# LoRa_RFM95_Shield.net
KiCad netlist of a schematic drawn in EAGLE
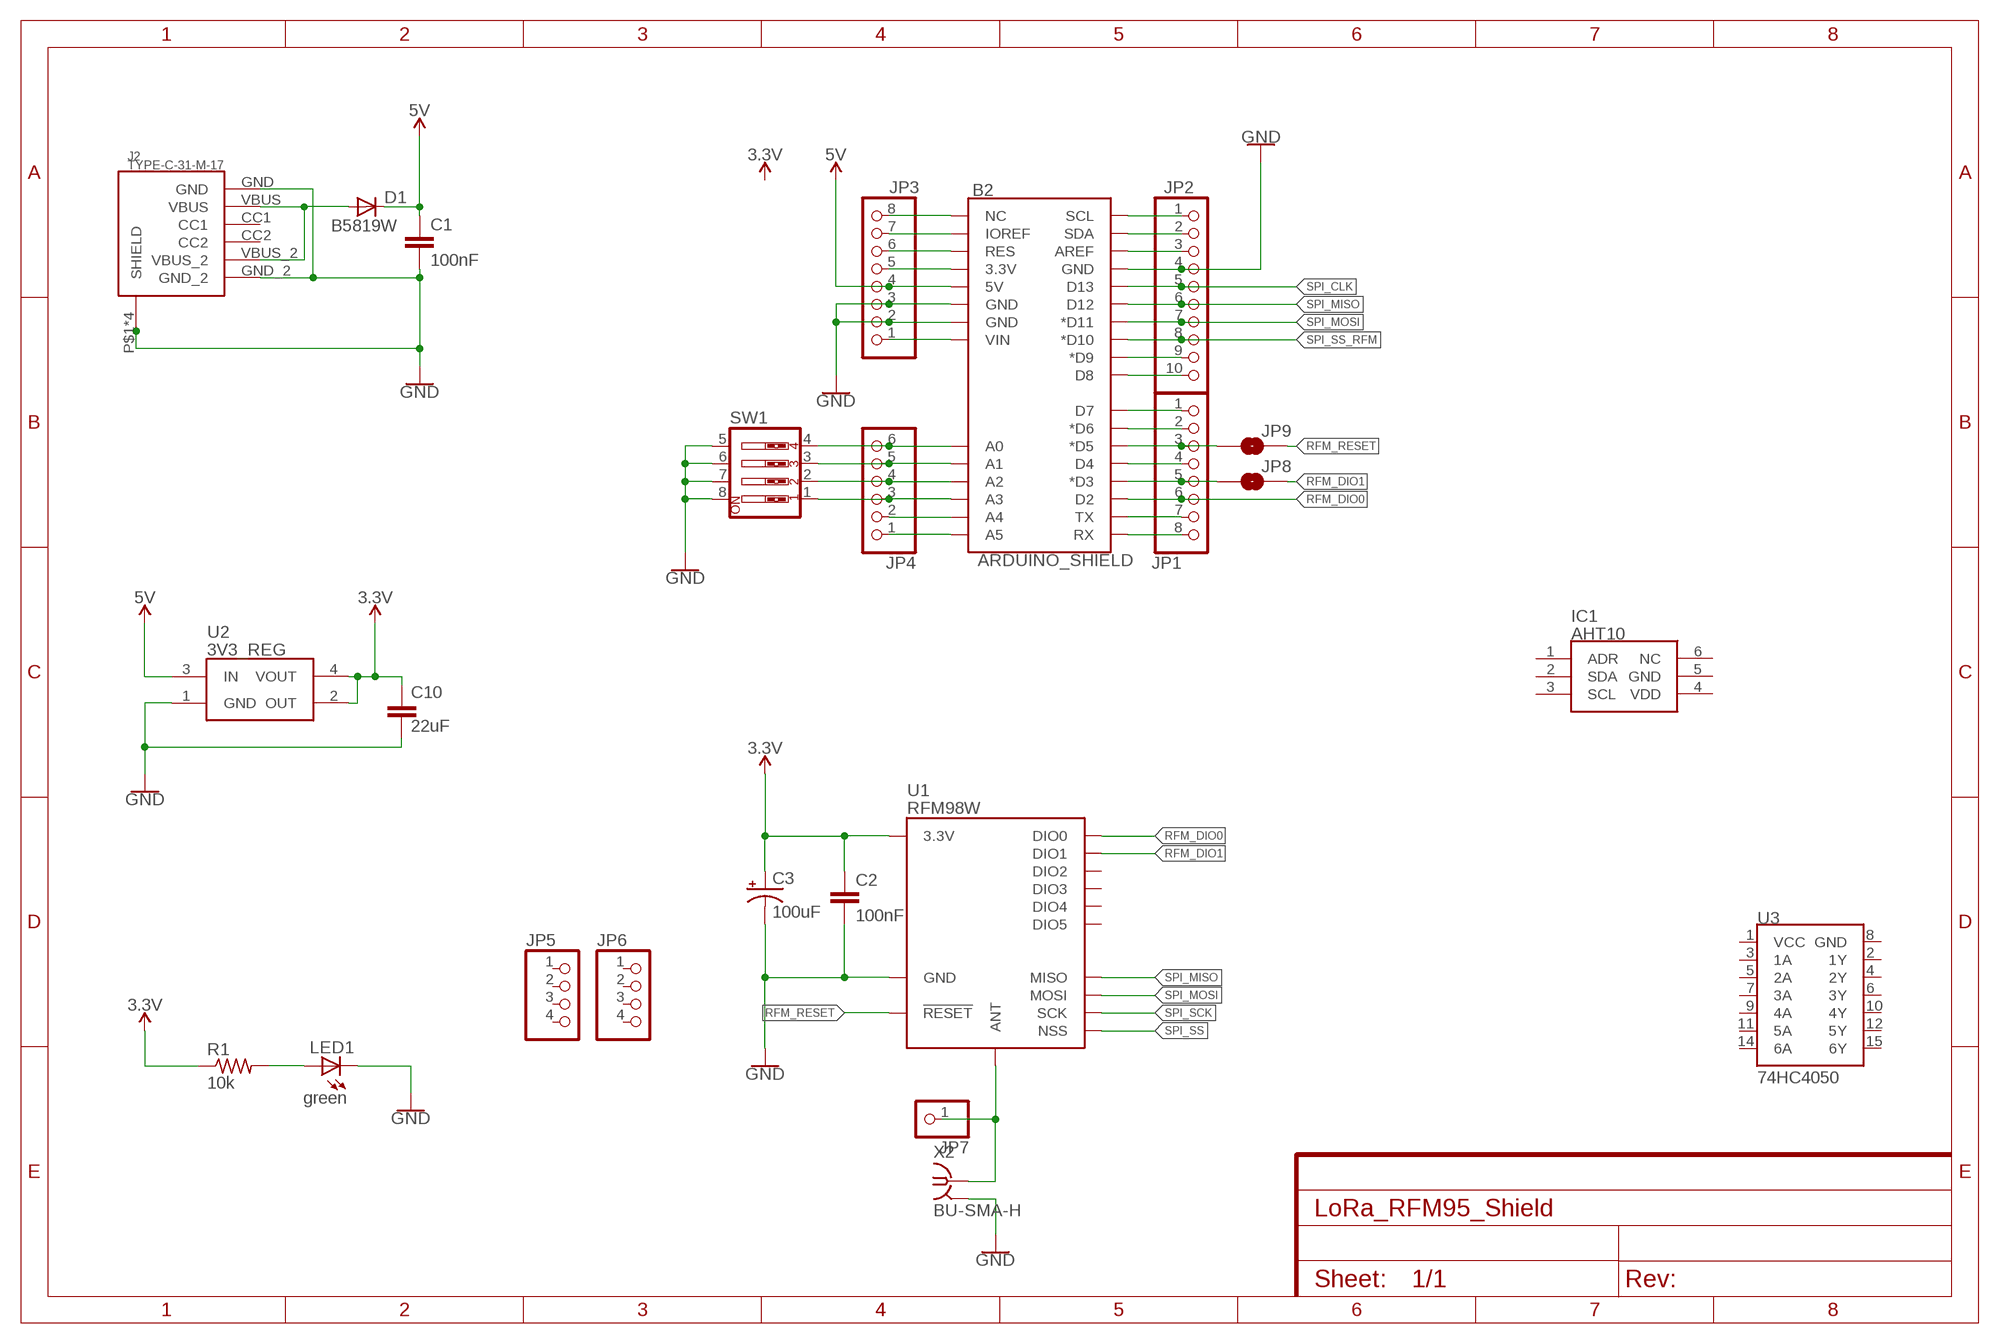
[diagram p0: schematic, sheet 1]

(export (version "E")
  (design (tool "Eeschema 10.0.6"))
  (components
    (comp (ref "B2")
      (value "ARDUINO_SHIELD")
      (footprint "eagle-import:UNO_R3_SHIELD_NOLABELS_LOCK")
      (libsource (lib "eagle-import") (part "ARDUINO_UNO_R3_SHIELDUNO_R3_SHIELD_NOLABELS_LOCK"))
    )
    (comp (ref "C1")
      (value "100nF")
      (footprint "eagle-import:C0603")
      (libsource (lib "eagle-import") (part "C-EUC0603"))
    )
    (comp (ref "C2")
      (value "100nF")
      (footprint "eagle-import:C0603")
      (libsource (lib "eagle-import") (part "C-EUC0603"))
    )
    (comp (ref "C3")
      (value "100uF")
      (footprint "eagle-import:SMC_B")
      (libsource (lib "eagle-import") (part "CPOL-USSMCB"))
    )
    (comp (ref "C10")
      (value "22uF")
      (footprint "eagle-import:C0805")
      (libsource (lib "eagle-import") (part "C-EUC0805"))
    )
    (comp (ref "D1")
      (value "B5819W")
      (footprint "eagle-import:SOD-123")
      (libsource (lib "eagle-import") (part "DIODE-SOD-123"))
    )
    (comp (ref "IC1")
      (value "AHT10")
      (footprint "eagle-import:AHT10")
      (libsource (lib "eagle-import") (part "AHT10"))
    )
    (comp (ref "J2")
      (value "TYPE-C-31-M-17")
      (footprint "eagle-import:TYPE-C-31-M-17")
      (libsource (lib "eagle-import") (part "TYPE-C-31-M-17"))
    )
    (comp (ref "JP1")
      (value "PINHD-1X8/OCT")
      (footprint "eagle-import:1X08_OCT")
      (libsource (lib "eagle-import") (part "PINHD-1X8/OCT"))
    )
    (comp (ref "JP2")
      (value "PINHD-1X10/OCT")
      (footprint "eagle-import:1X10_OCT")
      (libsource (lib "eagle-import") (part "PINHD-1X10/OCT"))
    )
    (comp (ref "JP3")
      (value "PINHD-1X8/OCT")
      (footprint "eagle-import:1X08_OCT")
      (libsource (lib "eagle-import") (part "PINHD-1X8/OCT"))
    )
    (comp (ref "JP4")
      (value "PINHD-1X6/OCT")
      (footprint "eagle-import:1X06_OCT")
      (libsource (lib "eagle-import") (part "PINHD-1X6/OCT"))
    )
    (comp (ref "JP5")
      (value "PINHD-1X4/OCT")
      (footprint "eagle-import:1X04_OCT")
      (libsource (lib "eagle-import") (part "PINHD-1X4/OCT"))
    )
    (comp (ref "JP6")
      (value "PINHD-1X4/OCT")
      (footprint "eagle-import:1X04_OCT")
      (libsource (lib "eagle-import") (part "PINHD-1X4/OCT"))
    )
    (comp (ref "JP7")
      (value "PINHD-1X1/OCT")
      (footprint "eagle-import:1X01_OCT")
      (libsource (lib "eagle-import") (part "PINHD-1X1/OCT"))
    )
    (comp (ref "JP8")
      (value "JUMPER-SMT_2_NO_SILK")
      (footprint "eagle-import:SMT-JUMPER_2_NO_SILK")
      (libsource (lib "eagle-import") (part "JUMPER-SMT_2_NO_SILK"))
    )
    (comp (ref "JP9")
      (value "JUMPER-SMT_2_NO_SILK")
      (footprint "eagle-import:SMT-JUMPER_2_NO_SILK")
      (libsource (lib "eagle-import") (part "JUMPER-SMT_2_NO_SILK"))
    )
    (comp (ref "LED1")
      (value "green")
      (footprint "eagle-import:CHIP-LED0603")
      (libsource (lib "eagle-import") (part "LEDCHIP-LED0603"))
    )
    (comp (ref "R1")
      (value "10k")
      (footprint "eagle-import:R0603")
      (libsource (lib "eagle-import") (part "R-US_R0603"))
    )
    (comp (ref "SW1")
      (value "SW_DIP-4")
      (footprint "eagle-import:EDG-04")
      (libsource (lib "eagle-import") (part "SW_DIP-4"))
    )
    (comp (ref "U1")
      (value "RFM98W")
      (footprint "eagle-import:RFM95_96_97_98W")
      (libsource (lib "eagle-import") (part "RFM95W"))
    )
    (comp (ref "U2")
      (value "3V3_REG")
      (footprint "eagle-import:SOT230P700X170-4N")
      (fields
        (field (name "MANUFACTURER_PART_NUMBER") "AZ1117H-5.0TRE1")
        (field (name "MOUSER_PART_NUMBER") "621-AZ1117H-5.0TRE1")
      )
      (libsource (lib "eagle-import") (part "AZ1117H-5.0TRE1"))
    )
    (comp (ref "U3")
      (value "74HC4050")
      (footprint "eagle-import:SO16")
      (libsource (lib "eagle-import") (part "HEX_CONVERTER"))
    )
    (comp (ref "X2")
      (value "BU-SMA-H")
      (footprint "eagle-import:BU-SMA-H")
      (libsource (lib "eagle-import") (part "BU-SMA-H"))
    )
  )
  (nets
    (net (code "1") (name "3.3V") (class "Default")
      (node (ref "C10") (pin "2") (pinfunction "2_2") (pintype "passive"))
      (node (ref "C2") (pin "1") (pinfunction "1_1") (pintype "passive"))
      (node (ref "C3") (pin "+") (pinfunction "+_+") (pintype "passive"))
      (node (ref "R1") (pin "1") (pinfunction "1_1") (pintype "passive"))
      (node (ref "U1") (pin "3.3V") (pinfunction "3.3V_3.3V") (pintype "bidirectional"))
      (node (ref "U2") (pin "2") (pinfunction "OUT_2") (pintype "bidirectional"))
      (node (ref "U2") (pin "4") (pinfunction "VOUT_4") (pintype "bidirectional"))
    )
    (net (code "2") (name "5V") (class "Default")
      (node (ref "B2") (pin "5V") (pinfunction "5V_5V") (pintype "bidirectional"))
      (node (ref "C1") (pin "1") (pinfunction "1_1") (pintype "passive"))
      (node (ref "D1") (pin "C") (pinfunction "C_C") (pintype "passive"))
      (node (ref "JP3") (pin "4") (pinfunction "4_4") (pintype "passive"))
      (node (ref "U2") (pin "3") (pinfunction "IN_3") (pintype "bidirectional"))
    )
    (net (code "3") (name "GND") (class "Default")
      (node (ref "B2") (pin "GND@0") (pinfunction "GND_GND@0") (pintype "bidirectional"))
      (node (ref "B2") (pin "GND@1") (pinfunction "GND_GND@1") (pintype "bidirectional"))
      (node (ref "B2") (pin "GND@2") (pinfunction "GND_GND@2") (pintype "bidirectional"))
      (node (ref "C1") (pin "2") (pinfunction "2_2") (pintype "passive"))
      (node (ref "C10") (pin "1") (pinfunction "1_1") (pintype "passive"))
      (node (ref "C2") (pin "2") (pinfunction "2_2") (pintype "passive"))
      (node (ref "C3") (pin "-") (pinfunction "-_-") (pintype "passive"))
      (node (ref "J2") (pin "GND") (pinfunction "GND_GND") (pintype "bidirectional"))
      (node (ref "J2") (pin "GND_2") (pinfunction "GND_2_GND_2") (pintype "bidirectional"))
      (node (ref "J2") (pin "P$1") (pinfunction "SHIELD_P$1") (pintype "bidirectional"))
      (node (ref "J2") (pin "P$2") (pinfunction "SHIELD_P$2") (pintype "bidirectional"))
      (node (ref "J2") (pin "P$3") (pinfunction "SHIELD_P$3") (pintype "bidirectional"))
      (node (ref "J2") (pin "P$4") (pinfunction "SHIELD_P$4") (pintype "bidirectional"))
      (node (ref "JP2") (pin "4") (pinfunction "4_4") (pintype "passive"))
      (node (ref "JP3") (pin "2") (pinfunction "2_2") (pintype "passive"))
      (node (ref "JP3") (pin "3") (pinfunction "3_3") (pintype "passive"))
      (node (ref "LED1") (pin "C") (pinfunction "C_C") (pintype "passive"))
      (node (ref "SW1") (pin "5") (pinfunction "5_5") (pintype "passive"))
      (node (ref "SW1") (pin "6") (pinfunction "6_6") (pintype "passive"))
      (node (ref "SW1") (pin "7") (pinfunction "7_7") (pintype "passive"))
      (node (ref "SW1") (pin "8") (pinfunction "8_8") (pintype "passive"))
      (node (ref "U1") (pin "GND@1") (pinfunction "GND_GND@1") (pintype "bidirectional"))
      (node (ref "U1") (pin "GND@2") (pinfunction "GND_GND@2") (pintype "bidirectional"))
      (node (ref "U1") (pin "GND@3") (pinfunction "GND_GND@3") (pintype "bidirectional"))
      (node (ref "U2") (pin "1") (pinfunction "GND_1") (pintype "bidirectional"))
      (node (ref "X2") (pin "2") (pinfunction "2_2") (pintype "passive"))
      (node (ref "X2") (pin "3") (pinfunction "2_3") (pintype "passive"))
      (node (ref "X2") (pin "4") (pinfunction "2_4") (pintype "passive"))
      (node (ref "X2") (pin "5") (pinfunction "2_5") (pintype "passive"))
    )
    (net (code "4") (name "Net-(B2-*D3)") (class "Default")
      (node (ref "B2") (pin "D3") (pinfunction "*D3_D3") (pintype "bidirectional"))
      (node (ref "JP1") (pin "5") (pinfunction "5_5") (pintype "passive"))
      (node (ref "JP8") (pin "1") (pinfunction "1_1") (pintype "passive"))
    )
    (net (code "5") (name "Net-(B2-*D5)") (class "Default")
      (node (ref "B2") (pin "D5") (pinfunction "*D5_D5") (pintype "bidirectional"))
      (node (ref "JP1") (pin "3") (pinfunction "3_3") (pintype "passive"))
      (node (ref "JP9") (pin "1") (pinfunction "1_1") (pintype "passive"))
    )
    (net (code "6") (name "Net-(B2-*D6)") (class "Default")
      (node (ref "B2") (pin "D6") (pinfunction "*D6_D6") (pintype "bidirectional"))
      (node (ref "JP1") (pin "2") (pinfunction "2_2") (pintype "passive"))
    )
    (net (code "7") (name "Net-(B2-*D9)") (class "Default")
      (node (ref "B2") (pin "D9") (pinfunction "*D9_D9") (pintype "bidirectional"))
      (node (ref "JP2") (pin "9") (pinfunction "9_9") (pintype "passive"))
    )
    (net (code "8") (name "Net-(B2-Pad3.3V)") (class "Default")
      (node (ref "B2") (pin "3.3V") (pinfunction "3.3V_3.3V") (pintype "bidirectional"))
      (node (ref "JP3") (pin "5") (pinfunction "5_5") (pintype "passive"))
    )
    (net (code "9") (name "Net-(B2-PadA0)") (class "Default")
      (node (ref "B2") (pin "A0") (pinfunction "A0_A0") (pintype "bidirectional"))
      (node (ref "JP4") (pin "6") (pinfunction "6_6") (pintype "passive"))
      (node (ref "SW1") (pin "4") (pinfunction "4_4") (pintype "passive"))
    )
    (net (code "10") (name "Net-(B2-PadA1)") (class "Default")
      (node (ref "B2") (pin "A1") (pinfunction "A1_A1") (pintype "bidirectional"))
      (node (ref "JP4") (pin "5") (pinfunction "5_5") (pintype "passive"))
      (node (ref "SW1") (pin "3") (pinfunction "3_3") (pintype "passive"))
    )
    (net (code "11") (name "Net-(B2-PadA2)") (class "Default")
      (node (ref "B2") (pin "A2") (pinfunction "A2_A2") (pintype "bidirectional"))
      (node (ref "JP4") (pin "4") (pinfunction "4_4") (pintype "passive"))
      (node (ref "SW1") (pin "2") (pinfunction "2_2") (pintype "passive"))
    )
    (net (code "12") (name "Net-(B2-PadA3)") (class "Default")
      (node (ref "B2") (pin "A3") (pinfunction "A3_A3") (pintype "bidirectional"))
      (node (ref "JP4") (pin "3") (pinfunction "3_3") (pintype "passive"))
      (node (ref "SW1") (pin "1") (pinfunction "1_1") (pintype "passive"))
    )
    (net (code "13") (name "Net-(B2-PadA4)") (class "Default")
      (node (ref "B2") (pin "A4") (pinfunction "A4_A4") (pintype "bidirectional"))
      (node (ref "JP4") (pin "2") (pinfunction "2_2") (pintype "passive"))
    )
    (net (code "14") (name "Net-(B2-PadA5)") (class "Default")
      (node (ref "B2") (pin "A5") (pinfunction "A5_A5") (pintype "bidirectional"))
      (node (ref "JP4") (pin "1") (pinfunction "1_1") (pintype "passive"))
    )
    (net (code "15") (name "Net-(B2-PadAREF)") (class "Default")
      (node (ref "B2") (pin "AREF") (pinfunction "AREF_AREF") (pintype "bidirectional"))
      (node (ref "JP2") (pin "3") (pinfunction "3_3") (pintype "passive"))
    )
    (net (code "16") (name "Net-(B2-PadD4)") (class "Default")
      (node (ref "B2") (pin "D4") (pinfunction "D4_D4") (pintype "bidirectional"))
      (node (ref "JP1") (pin "4") (pinfunction "4_4") (pintype "passive"))
    )
    (net (code "17") (name "Net-(B2-PadD7)") (class "Default")
      (node (ref "B2") (pin "D7") (pinfunction "D7_D7") (pintype "bidirectional"))
      (node (ref "JP1") (pin "1") (pinfunction "1_1") (pintype "passive"))
    )
    (net (code "18") (name "Net-(B2-PadD8)") (class "Default")
      (node (ref "B2") (pin "D8") (pinfunction "D8_D8") (pintype "bidirectional"))
      (node (ref "JP2") (pin "10") (pinfunction "10_10") (pintype "passive"))
    )
    (net (code "19") (name "Net-(B2-PadIOREF)") (class "Default")
      (node (ref "B2") (pin "IOREF") (pinfunction "IOREF_IOREF") (pintype "bidirectional"))
      (node (ref "JP3") (pin "7") (pinfunction "7_7") (pintype "passive"))
    )
    (net (code "20") (name "Net-(B2-PadNC)") (class "Default")
      (node (ref "B2") (pin "NC") (pinfunction "NC_NC") (pintype "bidirectional"))
      (node (ref "JP3") (pin "8") (pinfunction "8_8") (pintype "passive"))
    )
    (net (code "21") (name "Net-(B2-PadRES)") (class "Default")
      (node (ref "B2") (pin "RES") (pinfunction "RES_RES") (pintype "bidirectional"))
      (node (ref "JP3") (pin "6") (pinfunction "6_6") (pintype "passive"))
    )
    (net (code "22") (name "Net-(B2-PadRX)") (class "Default")
      (node (ref "B2") (pin "RX") (pinfunction "RX_RX") (pintype "bidirectional"))
      (node (ref "JP1") (pin "8") (pinfunction "8_8") (pintype "passive"))
    )
    (net (code "23") (name "Net-(B2-PadSCL)") (class "Default")
      (node (ref "B2") (pin "SCL") (pinfunction "SCL_SCL") (pintype "bidirectional"))
      (node (ref "JP2") (pin "1") (pinfunction "1_1") (pintype "passive"))
    )
    (net (code "24") (name "Net-(B2-PadSDA)") (class "Default")
      (node (ref "B2") (pin "SDA") (pinfunction "SDA_SDA") (pintype "bidirectional"))
      (node (ref "JP2") (pin "2") (pinfunction "2_2") (pintype "passive"))
    )
    (net (code "25") (name "Net-(B2-PadTX)") (class "Default")
      (node (ref "B2") (pin "TX") (pinfunction "TX_TX") (pintype "bidirectional"))
      (node (ref "JP1") (pin "7") (pinfunction "7_7") (pintype "passive"))
    )
    (net (code "26") (name "Net-(B2-PadVIN)") (class "Default")
      (node (ref "B2") (pin "VIN") (pinfunction "VIN_VIN") (pintype "bidirectional"))
      (node (ref "JP3") (pin "1") (pinfunction "1_1") (pintype "passive"))
    )
    (net (code "27") (name "Net-(D1-PadA)") (class "Default")
      (node (ref "D1") (pin "A") (pinfunction "A_A") (pintype "passive"))
      (node (ref "J2") (pin "VBUS") (pinfunction "VBUS_VBUS") (pintype "bidirectional"))
      (node (ref "J2") (pin "VBUS_2") (pinfunction "VBUS_2_VBUS_2") (pintype "bidirectional"))
    )
    (net (code "28") (name "Net-(JP7-Pad1)") (class "Default")
      (node (ref "JP7") (pin "1") (pinfunction "1_1") (pintype "passive"))
      (node (ref "U1") (pin "ANT") (pinfunction "ANT_ANT") (pintype "bidirectional"))
      (node (ref "X2") (pin "1") (pinfunction "1_1") (pintype "passive"))
    )
    (net (code "29") (name "Net-(LED1-PadA)") (class "Default")
      (node (ref "LED1") (pin "A") (pinfunction "A_A") (pintype "passive"))
      (node (ref "R1") (pin "2") (pinfunction "2_2") (pintype "passive"))
    )
    (net (code "30") (name "RFM_DIO0") (class "Default")
      (node (ref "B2") (pin "D2") (pinfunction "D2_D2") (pintype "bidirectional"))
      (node (ref "JP1") (pin "6") (pinfunction "6_6") (pintype "passive"))
      (node (ref "U1") (pin "DIO0") (pinfunction "DIO0_DIO0") (pintype "bidirectional"))
    )
    (net (code "31") (name "RFM_DIO1") (class "Default")
      (node (ref "JP8") (pin "2") (pinfunction "2_2") (pintype "passive"))
      (node (ref "U1") (pin "DIO1") (pinfunction "DIO1_DIO1") (pintype "bidirectional"))
    )
    (net (code "32") (name "RFM_RESET") (class "Default")
      (node (ref "JP9") (pin "2") (pinfunction "2_2") (pintype "passive"))
      (node (ref "U1") (pin "!RESET") (pinfunction "~{RESET}_!RESET") (pintype "bidirectional"))
    )
    (net (code "33") (name "SPI_CLK") (class "Default")
      (node (ref "B2") (pin "D13") (pinfunction "D13_D13") (pintype "bidirectional"))
      (node (ref "JP2") (pin "5") (pinfunction "5_5") (pintype "passive"))
    )
    (net (code "34") (name "SPI_MISO") (class "Default")
      (node (ref "B2") (pin "D12") (pinfunction "D12_D12") (pintype "bidirectional"))
      (node (ref "JP2") (pin "6") (pinfunction "6_6") (pintype "passive"))
      (node (ref "U1") (pin "MISO") (pinfunction "MISO_MISO") (pintype "bidirectional"))
    )
    (net (code "35") (name "SPI_MOSI") (class "Default")
      (node (ref "B2") (pin "D11") (pinfunction "*D11_D11") (pintype "bidirectional"))
      (node (ref "JP2") (pin "7") (pinfunction "7_7") (pintype "passive"))
      (node (ref "U1") (pin "MOSI") (pinfunction "MOSI_MOSI") (pintype "bidirectional"))
    )
    (net (code "36") (name "SPI_SCK") (class "Default")
      (node (ref "U1") (pin "SCK") (pinfunction "SCK_SCK") (pintype "bidirectional"))
    )
    (net (code "37") (name "SPI_SS") (class "Default")
      (node (ref "U1") (pin "NSS") (pinfunction "NSS_NSS") (pintype "bidirectional"))
    )
    (net (code "38") (name "SPI_SS_RFM") (class "Default")
      (node (ref "B2") (pin "D10") (pinfunction "*D10_D10") (pintype "bidirectional"))
      (node (ref "JP2") (pin "8") (pinfunction "8_8") (pintype "passive"))
    )
    (net (code "39") (name "unconnected-(IC1-ADR-Pad1)") (class "Default")
      (node (ref "IC1") (pin "1") (pinfunction "ADR_1") (pintype "bidirectional"))
    )
    (net (code "40") (name "unconnected-(IC1-GND-Pad5)") (class "Default")
      (node (ref "IC1") (pin "5") (pinfunction "GND_5") (pintype "bidirectional"))
    )
    (net (code "41") (name "unconnected-(IC1-NC-Pad6)") (class "Default")
      (node (ref "IC1") (pin "6") (pinfunction "NC_6") (pintype "no_connect"))
    )
    (net (code "42") (name "unconnected-(IC1-SCL-Pad3)") (class "Default")
      (node (ref "IC1") (pin "3") (pinfunction "SCL_3") (pintype "bidirectional"))
    )
    (net (code "43") (name "unconnected-(IC1-SDA-Pad2)") (class "Default")
      (node (ref "IC1") (pin "2") (pinfunction "SDA_2") (pintype "bidirectional"))
    )
    (net (code "44") (name "unconnected-(IC1-VDD-Pad4)") (class "Default")
      (node (ref "IC1") (pin "4") (pinfunction "VDD_4") (pintype "bidirectional"))
    )
    (net (code "45") (name "unconnected-(J2-PadCC1)") (class "Default")
      (node (ref "J2") (pin "CC1") (pinfunction "CC1_CC1") (pintype "bidirectional"))
    )
    (net (code "46") (name "unconnected-(J2-PadCC2)") (class "Default")
      (node (ref "J2") (pin "CC2") (pinfunction "CC2_CC2") (pintype "bidirectional"))
    )
    (net (code "47") (name "unconnected-(JP5-Pad1)") (class "Default")
      (node (ref "JP5") (pin "1") (pinfunction "1_1") (pintype "passive"))
    )
    (net (code "48") (name "unconnected-(JP5-Pad2)") (class "Default")
      (node (ref "JP5") (pin "2") (pinfunction "2_2") (pintype "passive"))
    )
    (net (code "49") (name "unconnected-(JP5-Pad3)") (class "Default")
      (node (ref "JP5") (pin "3") (pinfunction "3_3") (pintype "passive"))
    )
    (net (code "50") (name "unconnected-(JP5-Pad4)") (class "Default")
      (node (ref "JP5") (pin "4") (pinfunction "4_4") (pintype "passive"))
    )
    (net (code "51") (name "unconnected-(JP6-Pad1)") (class "Default")
      (node (ref "JP6") (pin "1") (pinfunction "1_1") (pintype "passive"))
    )
    (net (code "52") (name "unconnected-(JP6-Pad2)") (class "Default")
      (node (ref "JP6") (pin "2") (pinfunction "2_2") (pintype "passive"))
    )
    (net (code "53") (name "unconnected-(JP6-Pad3)") (class "Default")
      (node (ref "JP6") (pin "3") (pinfunction "3_3") (pintype "passive"))
    )
    (net (code "54") (name "unconnected-(JP6-Pad4)") (class "Default")
      (node (ref "JP6") (pin "4") (pinfunction "4_4") (pintype "passive"))
    )
    (net (code "55") (name "unconnected-(U1-PadDIO2)") (class "Default")
      (node (ref "U1") (pin "DIO2") (pinfunction "DIO2_DIO2") (pintype "bidirectional"))
    )
    (net (code "56") (name "unconnected-(U1-PadDIO3)") (class "Default")
      (node (ref "U1") (pin "DIO3") (pinfunction "DIO3_DIO3") (pintype "bidirectional"))
    )
    (net (code "57") (name "unconnected-(U1-PadDIO4)") (class "Default")
      (node (ref "U1") (pin "DIO4") (pinfunction "DIO4_DIO4") (pintype "bidirectional"))
    )
    (net (code "58") (name "unconnected-(U1-PadDIO5)") (class "Default")
      (node (ref "U1") (pin "DIO5") (pinfunction "DIO5_DIO5") (pintype "bidirectional"))
    )
    (net (code "59") (name "unconnected-(U3-1A-Pad3)") (class "Default")
      (node (ref "U3") (pin "3") (pinfunction "1A_3") (pintype "bidirectional"))
    )
    (net (code "60") (name "unconnected-(U3-1Y-Pad2)") (class "Default")
      (node (ref "U3") (pin "2") (pinfunction "1Y_2") (pintype "bidirectional"))
    )
    (net (code "61") (name "unconnected-(U3-2A-Pad5)") (class "Default")
      (node (ref "U3") (pin "5") (pinfunction "2A_5") (pintype "bidirectional"))
    )
    (net (code "62") (name "unconnected-(U3-2Y-Pad4)") (class "Default")
      (node (ref "U3") (pin "4") (pinfunction "2Y_4") (pintype "bidirectional"))
    )
    (net (code "63") (name "unconnected-(U3-3A-Pad7)") (class "Default")
      (node (ref "U3") (pin "7") (pinfunction "3A_7") (pintype "bidirectional"))
    )
    (net (code "64") (name "unconnected-(U3-3Y-Pad6)") (class "Default")
      (node (ref "U3") (pin "6") (pinfunction "3Y_6") (pintype "bidirectional"))
    )
    (net (code "65") (name "unconnected-(U3-4A-Pad9)") (class "Default")
      (node (ref "U3") (pin "9") (pinfunction "4A_9") (pintype "bidirectional"))
    )
    (net (code "66") (name "unconnected-(U3-4Y-Pad10)") (class "Default")
      (node (ref "U3") (pin "10") (pinfunction "4Y_10") (pintype "bidirectional"))
    )
    (net (code "67") (name "unconnected-(U3-5A-Pad11)") (class "Default")
      (node (ref "U3") (pin "11") (pinfunction "5A_11") (pintype "bidirectional"))
    )
    (net (code "68") (name "unconnected-(U3-5Y-Pad12)") (class "Default")
      (node (ref "U3") (pin "12") (pinfunction "5Y_12") (pintype "bidirectional"))
    )
    (net (code "69") (name "unconnected-(U3-6A-Pad14)") (class "Default")
      (node (ref "U3") (pin "14") (pinfunction "6A_14") (pintype "bidirectional"))
    )
    (net (code "70") (name "unconnected-(U3-6Y-Pad15)") (class "Default")
      (node (ref "U3") (pin "15") (pinfunction "6Y_15") (pintype "bidirectional"))
    )
    (net (code "71") (name "unconnected-(U3-GND-Pad8)") (class "Default")
      (node (ref "U3") (pin "8") (pinfunction "GND_8") (pintype "bidirectional"))
    )
    (net (code "72") (name "unconnected-(U3-VCC-Pad1)") (class "Default")
      (node (ref "U3") (pin "1") (pinfunction "VCC_1") (pintype "bidirectional"))
    )
  )
)
